# Power.net
KiCad netlist of a schematic drawn in Altium Designer
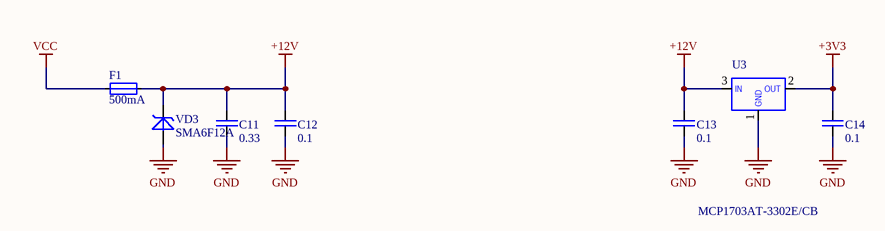
[diagram p0: Power.SchDoc]

(export (version "E")
  (design (tool "Eeschema 10.0.6"))
  (components
    (comp (ref "C11")
      (value "0.33")
      (footprint "DISCRETE:CAP_0805")
      (description "None polar capacitor")
      (libsource (lib "DISCRETE") (part "C_NONE_POLAR"))
    )
    (comp (ref "C12")
      (value "0.1")
      (footprint "DISCRETE:CAP_0805")
      (description "None polar capacitor")
      (libsource (lib "DISCRETE") (part "C_NONE_POLAR"))
    )
    (comp (ref "C13")
      (value "0.1")
      (footprint "DISCRETE:CAP_0805")
      (description "None polar capacitor")
      (libsource (lib "DISCRETE") (part "C_NONE_POLAR"))
    )
    (comp (ref "C14")
      (value "0.1")
      (footprint "DISCRETE:CAP_0805")
      (description "None polar capacitor")
      (libsource (lib "DISCRETE") (part "C_NONE_POLAR"))
    )
    (comp (ref "F1")
      (value "500mA")
      (footprint "DISCRETE:SMD_1206")
      (description "Resistor")
      (libsource (lib "DISCRETE") (part "FUSE"))
    )
    (comp (ref "U3")
      (value "MCP1703AT-3302E/CB")
      (footprint "ICs:SOT23-3")
      (description "250 mA, 16V, Low Quiescent Current LDO Regulator")
      (libsource (lib "ICs") (part "MCP1703A"))
    )
    (comp (ref "VD3")
      (value "SMA6F12A")
      (footprint "DISCRETE:DO-221AC")
      (description "TVS Diode")
      (libsource (lib "DISCRETE") (part "DIOSE_TVS"))
    )
  )
  (nets
    (net (code "1") (name "+3V3") (class "Default")
      (node (ref "C14") (pin "1") (pintype "passive"))
      (node (ref "U3") (pin "2") (pinfunction "OUT_2") (pintype "power_in"))
    )
    (net (code "2") (name "+12V") (class "Default")
      (node (ref "C11") (pin "1") (pintype "passive"))
      (node (ref "C12") (pin "1") (pintype "passive"))
      (node (ref "C13") (pin "1") (pintype "passive"))
      (node (ref "F1") (pin "1") (pintype "passive"))
      (node (ref "U3") (pin "3") (pinfunction "IN_3") (pintype "power_in"))
      (node (ref "VD3") (pin "1") (pinfunction "1_1") (pintype "passive"))
    )
    (net (code "3") (name "GND") (class "Default")
      (node (ref "C11") (pin "2") (pintype "passive"))
      (node (ref "C12") (pin "2") (pintype "passive"))
      (node (ref "C13") (pin "2") (pintype "passive"))
      (node (ref "C14") (pin "2") (pintype "passive"))
      (node (ref "U3") (pin "1") (pinfunction "GND_1") (pintype "passive"))
      (node (ref "VD3") (pin "2") (pinfunction "2_2") (pintype "passive"))
    )
    (net (code "4") (name "VCC") (class "Default") (node (ref "F1") (pin "2") (pintype "passive")))
  )
)
